# strobecontroller.net
KiCad netlist of a schematic drawn in EAGLE
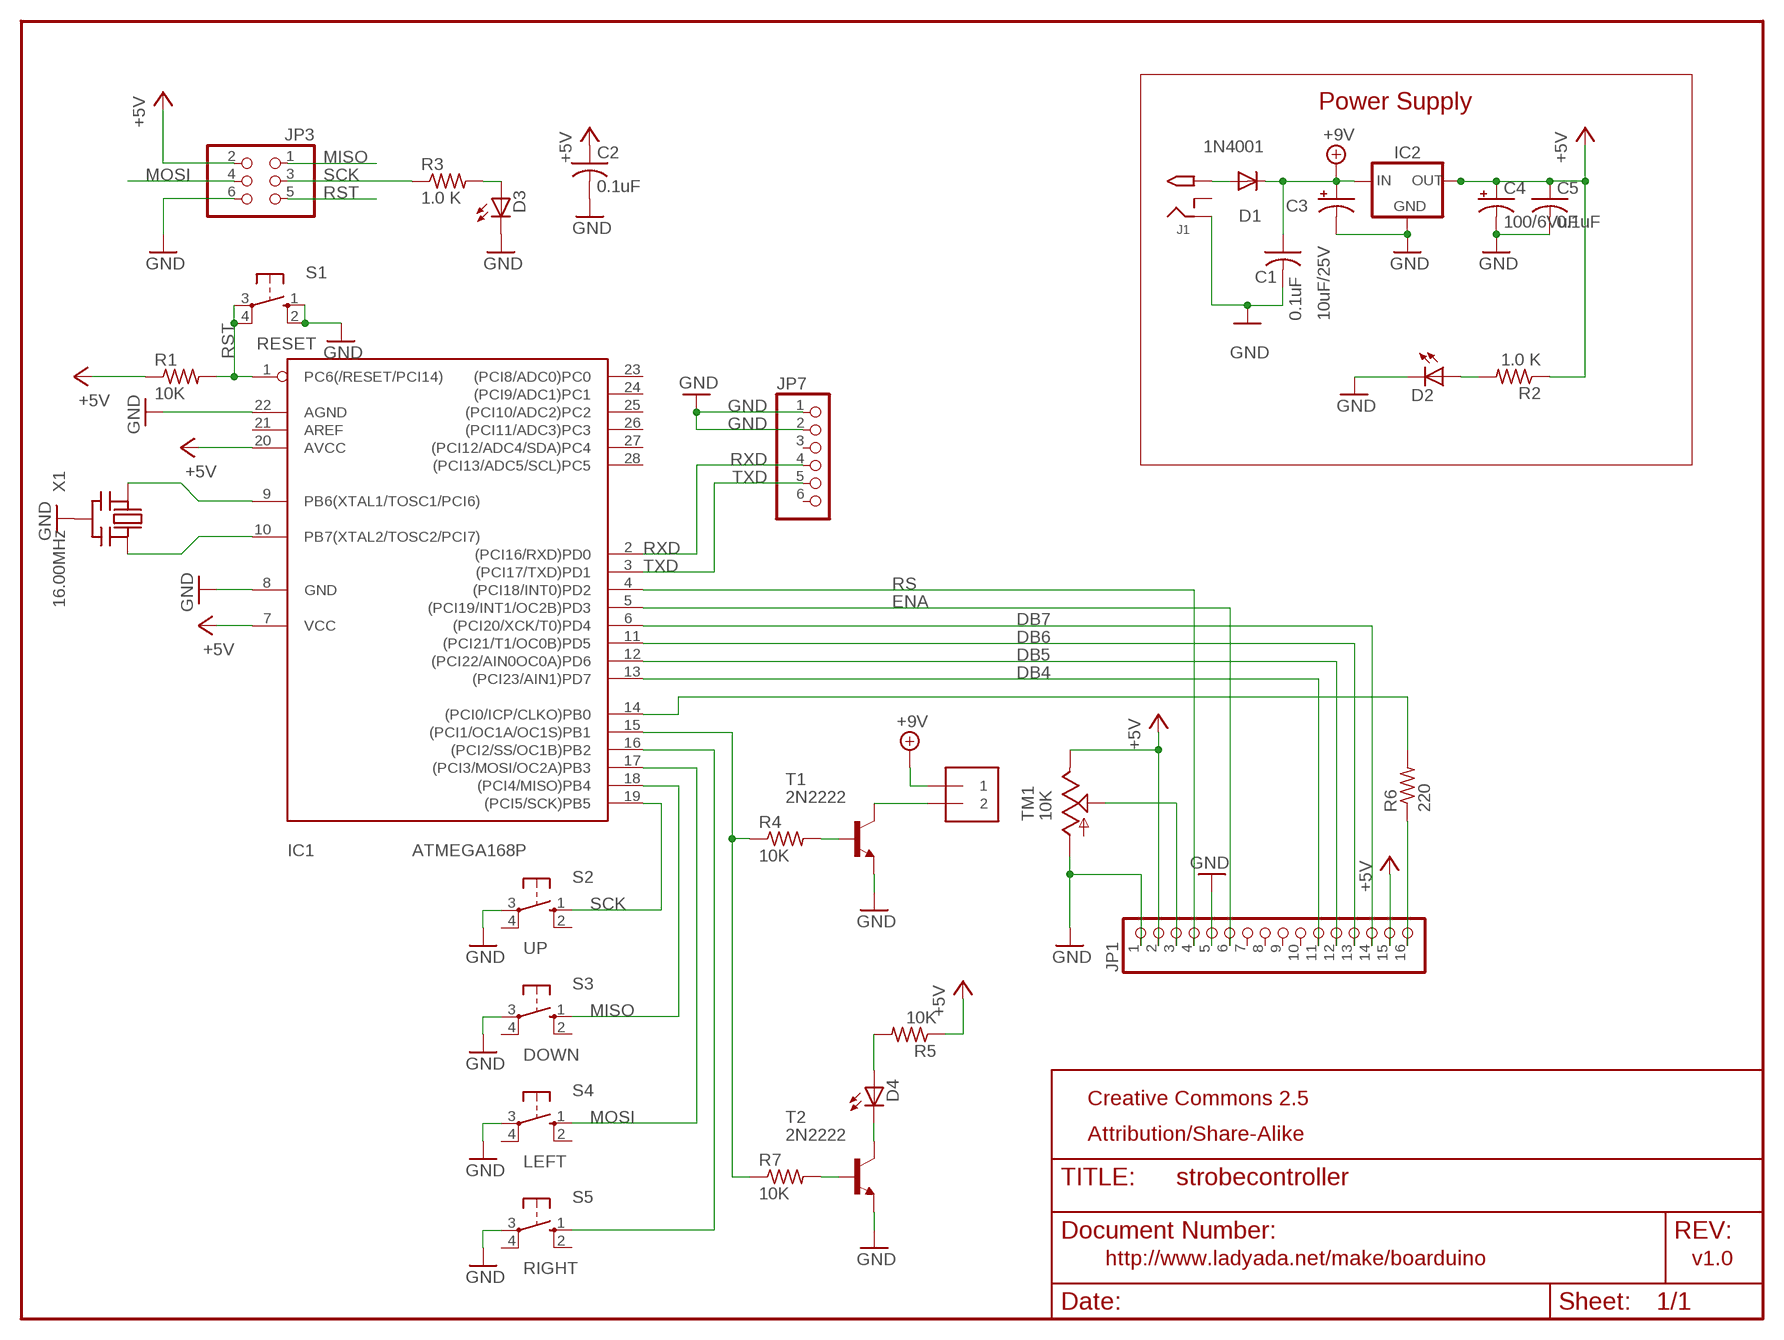
[diagram p0: schematic, sheet 1]

(export (version "E")
  (design (tool "Eeschema 10.0.6"))
  (components
    (comp (ref "C1")
      (value "0.1uF")
      (footprint "eagle-import:C025-025X050")
      (libsource (lib "eagle-import") (part "C-US025-025X050"))
    )
    (comp (ref "C2")
      (value "0.1uF")
      (footprint "eagle-import:C025-025X050")
      (libsource (lib "eagle-import") (part "C-US025-025X050"))
    )
    (comp (ref "C3")
      (value "10uF/25V")
      (footprint "eagle-import:E2,5-6")
      (libsource (lib "eagle-import") (part "CPOL-USE2.5-6"))
    )
    (comp (ref "C4")
      (value "100/6VuF")
      (footprint "eagle-import:E2,5-6")
      (libsource (lib "eagle-import") (part "CPOL-USE2.5-6"))
    )
    (comp (ref "C5")
      (value "0.1uF")
      (footprint "eagle-import:C025-025X050")
      (libsource (lib "eagle-import") (part "C-US025-025X050"))
    )
    (comp (ref "D1")
      (value "1N4001")
      (footprint "eagle-import:DO41-10")
      (libsource (lib "eagle-import") (part "1N4004"))
    )
    (comp (ref "D2")
      (value "Red")
      (footprint "eagle-import:LED3MM")
      (libsource (lib "eagle-import") (part "LED3MM"))
    )
    (comp (ref "D3")
      (value "Green")
      (footprint "eagle-import:LED3MM")
      (libsource (lib "eagle-import") (part "LED3MM"))
    )
    (comp (ref "D4")
      (value "Red")
      (footprint "eagle-import:LED3MM")
      (libsource (lib "eagle-import") (part "LED3MM"))
    )
    (comp (ref "IC1")
      (value "ATMEGA168P")
      (footprint "eagle-import:DIL28_3")
      (libsource (lib "eagle-import") (part "ATMEGA168PROUND"))
    )
    (comp (ref "IC2")
      (value "78XXS")
      (footprint "eagle-import:78XXS")
      (libsource (lib "eagle-import") (part "78XXS"))
    )
    (comp (ref "J1")
      (value "2.1MMJACK")
      (footprint "eagle-import:PJ-102A")
      (libsource (lib "eagle-import") (part "2.1MMJACK"))
    )
    (comp (ref "J2")
      (value "1X2-3.5MM")
      (footprint "eagle-import:1X2-3.5MM")
      (libsource (lib "eagle-import") (part "1X2-3.5MM"))
    )
    (comp (ref "JP1")
      (value "PINHD-1X16")
      (footprint "eagle-import:1X16")
      (libsource (lib "eagle-import") (part "PINHD-1X16"))
    )
    (comp (ref "JP3")
      (value "PINHD-2X3")
      (footprint "eagle-import:2X03")
      (libsource (lib "eagle-import") (part "PINHD-2X3"))
    )
    (comp (ref "JP7")
      (value "PINHD-1X6CLEAN")
      (footprint "eagle-import:1X06-CLEAN")
      (libsource (lib "eagle-import") (part "PINHD-1X6CLEAN"))
    )
    (comp (ref "R1")
      (value "10K")
      (footprint "eagle-import:0207_5V")
      (libsource (lib "eagle-import") (part "rcl-ez_R-US_0207/5V"))
    )
    (comp (ref "R2")
      (value "1.0 K")
      (footprint "eagle-import:0207_5V")
      (libsource (lib "eagle-import") (part "R-US_0207/5V"))
    )
    (comp (ref "R3")
      (value "1.0 K")
      (footprint "eagle-import:0207_5V")
      (libsource (lib "eagle-import") (part "R-US_0207/5V"))
    )
    (comp (ref "R4")
      (value "10K")
      (footprint "eagle-import:0207_5V")
      (libsource (lib "eagle-import") (part "rcl-ez_R-US_0207/5V"))
    )
    (comp (ref "R5")
      (value "10K")
      (footprint "eagle-import:0207_5V")
      (libsource (lib "eagle-import") (part "rcl-ez_R-US_0207/5V"))
    )
    (comp (ref "R6")
      (value "220")
      (footprint "eagle-import:0207_5V")
      (libsource (lib "eagle-import") (part "rcl-ez_R-US_0207/5V"))
    )
    (comp (ref "R7")
      (value "10K")
      (footprint "eagle-import:0207_5V")
      (libsource (lib "eagle-import") (part "rcl-ez_R-US_0207/5V"))
    )
    (comp (ref "S1")
      (value "RESET")
      (footprint "eagle-import:B3F-10XX")
      (libsource (lib "eagle-import") (part "10-XX"))
    )
    (comp (ref "S2")
      (value "UP")
      (footprint "eagle-import:B3F-10XX")
      (libsource (lib "eagle-import") (part "10-XX"))
    )
    (comp (ref "S3")
      (value "DOWN")
      (footprint "eagle-import:B3F-10XX")
      (libsource (lib "eagle-import") (part "10-XX"))
    )
    (comp (ref "S4")
      (value "LEFT")
      (footprint "eagle-import:B3F-10XX")
      (libsource (lib "eagle-import") (part "10-XX"))
    )
    (comp (ref "S5")
      (value "RIGHT")
      (footprint "eagle-import:B3F-10XX")
      (libsource (lib "eagle-import") (part "10-XX"))
    )
    (comp (ref "T1")
      (value "2N2222")
      (footprint "eagle-import:TO92-EBC-OVAL")
      (libsource (lib "eagle-import") (part "2N2222"))
    )
    (comp (ref "T2")
      (value "2N2222")
      (footprint "eagle-import:TO92-EBC-OVAL")
      (libsource (lib "eagle-import") (part "2N2222"))
    )
    (comp (ref "TM1")
      (value "10K")
      (footprint "eagle-import:6MM")
      (libsource (lib "eagle-import") (part "TRIM"))
    )
    (comp (ref "X1")
      (value "16.00MHz")
      (footprint "eagle-import:CERM_OSC")
      (libsource (lib "eagle-import") (part "CERMOSCILL"))
    )
  )
  (nets
    (net (code "1") (name "+5V") (class "Default")
      (node (ref "C2") (pin "1") (pinfunction "1_1") (pintype "passive"))
      (node (ref "C4") (pin "+") (pinfunction "+_+") (pintype "passive"))
      (node (ref "C5") (pin "1") (pinfunction "1_1") (pintype "passive"))
      (node (ref "IC1") (pin "20") (pinfunction "AVCC_20") (pintype "bidirectional"))
      (node (ref "IC1") (pin "7") (pinfunction "VCC_7") (pintype "bidirectional"))
      (node (ref "IC2") (pin "OUT") (pinfunction "OUT_OUT") (pintype "passive"))
      (node (ref "JP1") (pin "15") (pinfunction "15_15") (pintype "passive"))
      (node (ref "JP1") (pin "2") (pinfunction "2_2") (pintype "passive"))
      (node (ref "JP3") (pin "2") (pinfunction "2_2") (pintype "passive"))
      (node (ref "R1") (pin "1") (pinfunction "1_1") (pintype "passive"))
      (node (ref "R2") (pin "1") (pinfunction "1_1") (pintype "passive"))
      (node (ref "R5") (pin "1") (pinfunction "1_1") (pintype "passive"))
      (node (ref "TM1") (pin "E") (pinfunction "E_E") (pintype "passive"))
    )
    (net (code "2") (name "+9V") (class "Default")
      (node (ref "C1") (pin "1") (pinfunction "1_1") (pintype "passive"))
      (node (ref "C3") (pin "+") (pinfunction "+_+") (pintype "passive"))
      (node (ref "D1") (pin "C") (pinfunction "C_C") (pintype "passive"))
      (node (ref "IC2") (pin "IN") (pinfunction "IN_IN") (pintype "input"))
      (node (ref "J2") (pin "1") (pinfunction "1_1") (pintype "passive"))
    )
    (net (code "3") (name "/DB4") (class "Default")
      (node (ref "IC1") (pin "13") (pinfunction "(PCI23/AIN1)PD7_13") (pintype "bidirectional"))
      (node (ref "JP1") (pin "11") (pinfunction "11_11") (pintype "passive"))
    )
    (net (code "4") (name "/DB5") (class "Default")
      (node (ref "IC1") (pin "12") (pinfunction "(PCI22/AIN0OC0A)PD6_12") (pintype "bidirectional"))
      (node (ref "JP1") (pin "12") (pinfunction "12_12") (pintype "passive"))
    )
    (net (code "5") (name "/DB6") (class "Default")
      (node (ref "IC1") (pin "11") (pinfunction "(PCI21/T1/OC0B)PD5_11") (pintype "bidirectional"))
      (node (ref "JP1") (pin "13") (pinfunction "13_13") (pintype "passive"))
    )
    (net (code "6") (name "/DB7") (class "Default")
      (node (ref "IC1") (pin "6") (pinfunction "(PCI20/XCK/T0)PD4_6") (pintype "bidirectional"))
      (node (ref "JP1") (pin "14") (pinfunction "14_14") (pintype "passive"))
    )
    (net (code "7") (name "/ENA") (class "Default")
      (node (ref "IC1") (pin "5") (pinfunction "(PCI19/INT1/OC2B)PD3_5") (pintype "bidirectional"))
      (node (ref "JP1") (pin "6") (pinfunction "6_6") (pintype "passive"))
    )
    (net (code "8") (name "/MISO") (class "Default")
      (node (ref "IC1") (pin "18") (pinfunction "(PCI4/MISO)PB4_18") (pintype "bidirectional"))
      (node (ref "JP3") (pin "1") (pinfunction "1_1") (pintype "passive"))
      (node (ref "S3") (pin "1") (pinfunction "S_1") (pintype "passive"))
    )
    (net (code "9") (name "/MOSI") (class "Default")
      (node (ref "IC1") (pin "17") (pinfunction "(PCI3/MOSI/OC2A)PB3_17") (pintype "bidirectional"))
      (node (ref "JP3") (pin "4") (pinfunction "4_4") (pintype "passive"))
      (node (ref "S4") (pin "1") (pinfunction "S_1") (pintype "passive"))
    )
    (net (code "10") (name "/RS") (class "Default")
      (node (ref "IC1") (pin "4") (pinfunction "(PCI18/INT0)PD2_4") (pintype "bidirectional"))
      (node (ref "JP1") (pin "4") (pinfunction "4_4") (pintype "passive"))
    )
    (net (code "11") (name "/RST") (class "Default")
      (node (ref "IC1") (pin "1") (pinfunction "PC6(/RESET/PCI14)_1") (pintype "bidirectional"))
      (node (ref "JP3") (pin "5") (pinfunction "5_5") (pintype "passive"))
      (node (ref "R1") (pin "2") (pinfunction "2_2") (pintype "passive"))
      (node (ref "S1") (pin "3") (pinfunction "P_3") (pintype "passive"))
      (node (ref "S1") (pin "4") (pinfunction "P1_4") (pintype "passive"))
    )
    (net (code "12") (name "/RXD") (class "Default")
      (node (ref "IC1") (pin "2") (pinfunction "(PCI16/RXD)PD0_2") (pintype "bidirectional"))
      (node (ref "JP7") (pin "4") (pinfunction "4_4") (pintype "passive"))
    )
    (net (code "13") (name "/SCK") (class "Default")
      (node (ref "IC1") (pin "19") (pinfunction "(PCI5/SCK)PB5_19") (pintype "bidirectional"))
      (node (ref "JP3") (pin "3") (pinfunction "3_3") (pintype "passive"))
      (node (ref "R3") (pin "1") (pinfunction "1_1") (pintype "passive"))
      (node (ref "S2") (pin "1") (pinfunction "S_1") (pintype "passive"))
    )
    (net (code "14") (name "/TXD") (class "Default")
      (node (ref "IC1") (pin "3") (pinfunction "(PCI17/TXD)PD1_3") (pintype "bidirectional"))
      (node (ref "JP7") (pin "5") (pinfunction "5_5") (pintype "passive"))
    )
    (net (code "15") (name "GND") (class "Default")
      (node (ref "C1") (pin "2") (pinfunction "2_2") (pintype "passive"))
      (node (ref "C2") (pin "2") (pinfunction "2_2") (pintype "passive"))
      (node (ref "C3") (pin "-") (pinfunction "-_-") (pintype "passive"))
      (node (ref "C4") (pin "-") (pinfunction "-_-") (pintype "passive"))
      (node (ref "C5") (pin "2") (pinfunction "2_2") (pintype "passive"))
      (node (ref "D2") (pin "K") (pinfunction "C_K") (pintype "passive"))
      (node (ref "D3") (pin "K") (pinfunction "C_K") (pintype "passive"))
      (node (ref "IC1") (pin "22") (pinfunction "AGND_22") (pintype "bidirectional"))
      (node (ref "IC1") (pin "8") (pinfunction "GND_8") (pintype "bidirectional"))
      (node (ref "IC2") (pin "GND") (pinfunction "GND_GND") (pintype "input"))
      (node (ref "J1") (pin "RING") (pinfunction "RING_RING") (pintype "bidirectional"))
      (node (ref "JP1") (pin "1") (pinfunction "1_1") (pintype "passive"))
      (node (ref "JP1") (pin "5") (pinfunction "5_5") (pintype "passive"))
      (node (ref "JP3") (pin "6") (pinfunction "6_6") (pintype "passive"))
      (node (ref "JP7") (pin "1") (pinfunction "1_1") (pintype "passive"))
      (node (ref "JP7") (pin "2") (pinfunction "2_2") (pintype "passive"))
      (node (ref "S1") (pin "1") (pinfunction "S_1") (pintype "passive"))
      (node (ref "S1") (pin "2") (pinfunction "S1_2") (pintype "passive"))
      (node (ref "S2") (pin "3") (pinfunction "P_3") (pintype "passive"))
      (node (ref "S3") (pin "3") (pinfunction "P_3") (pintype "passive"))
      (node (ref "S4") (pin "3") (pinfunction "P_3") (pintype "passive"))
      (node (ref "S5") (pin "3") (pinfunction "P_3") (pintype "passive"))
      (node (ref "T1") (pin "E") (pinfunction "E_E") (pintype "passive"))
      (node (ref "T2") (pin "E") (pinfunction "E_E") (pintype "passive"))
      (node (ref "TM1") (pin "A") (pinfunction "A_A") (pintype "passive"))
      (node (ref "X1") (pin "P$2") (pinfunction "GND_P$2") (pintype "bidirectional"))
    )
    (net (code "16") (name "Net-(D1-PadA)") (class "Default")
      (node (ref "D1") (pin "A") (pinfunction "A_A") (pintype "passive"))
      (node (ref "J1") (pin "TIP") (pinfunction "TIP_TIP") (pintype "bidirectional"))
    )
    (net (code "17") (name "Net-(D2-PadA)") (class "Default")
      (node (ref "D2") (pin "A") (pinfunction "A_A") (pintype "passive"))
      (node (ref "R2") (pin "2") (pinfunction "2_2") (pintype "passive"))
    )
    (net (code "18") (name "Net-(D3-PadA)") (class "Default")
      (node (ref "D3") (pin "A") (pinfunction "A_A") (pintype "passive"))
      (node (ref "R3") (pin "2") (pinfunction "2_2") (pintype "passive"))
    )
    (net (code "19") (name "Net-(D4-C)") (class "Default")
      (node (ref "D4") (pin "K") (pinfunction "C_K") (pintype "passive"))
      (node (ref "T2") (pin "C") (pinfunction "C_C") (pintype "passive"))
    )
    (net (code "20") (name "Net-(D4-PadA)") (class "Default")
      (node (ref "D4") (pin "A") (pinfunction "A_A") (pintype "passive"))
      (node (ref "R5") (pin "2") (pinfunction "2_2") (pintype "passive"))
    )
    (net (code "21") (name "Net-(IC1-(PCI0{slash}ICP{slash}CLKO)PB0)") (class "Default")
      (node (ref "IC1") (pin "14") (pinfunction "(PCI0/ICP/CLKO)PB0_14") (pintype "bidirectional"))
      (node (ref "R6") (pin "2") (pinfunction "2_2") (pintype "passive"))
    )
    (net (code "22") (name "Net-(IC1-(PCI1{slash}OC1A{slash}OC1S)PB1)") (class "Default")
      (node (ref "IC1") (pin "15") (pinfunction "(PCI1/OC1A/OC1S)PB1_15") (pintype "bidirectional"))
      (node (ref "R4") (pin "1") (pinfunction "1_1") (pintype "passive"))
      (node (ref "R7") (pin "1") (pinfunction "1_1") (pintype "passive"))
    )
    (net (code "23") (name "Net-(IC1-(PCI2{slash}SS{slash}OC1B)PB2)") (class "Default")
      (node (ref "IC1") (pin "16") (pinfunction "(PCI2/SS/OC1B)PB2_16") (pintype "bidirectional"))
      (node (ref "S5") (pin "1") (pinfunction "S_1") (pintype "passive"))
    )
    (net (code "24") (name "Net-(IC1-PB6(XTAL1{slash}TOSC1{slash}PCI6))") (class "Default")
      (node (ref "IC1") (pin "9") (pinfunction "PB6(XTAL1/TOSC1/PCI6)_9") (pintype "bidirectional"))
      (node (ref "X1") (pin "P$1") (pinfunction "IN_P$1") (pintype "bidirectional"))
    )
    (net (code "25") (name "Net-(IC1-PB7(XTAL2{slash}TOSC2{slash}PCI7))") (class "Default")
      (node (ref "IC1") (pin "10") (pinfunction "PB7(XTAL2/TOSC2/PCI7)_10") (pintype "bidirectional"))
      (node (ref "X1") (pin "P$3") (pinfunction "OUT_P$3") (pintype "bidirectional"))
    )
    (net (code "26") (name "Net-(J2-Pad2)") (class "Default")
      (node (ref "J2") (pin "2") (pinfunction "2_2") (pintype "passive"))
      (node (ref "T1") (pin "C") (pinfunction "C_C") (pintype "passive"))
    )
    (net (code "27") (name "Net-(JP1-Pad3)") (class "Default")
      (node (ref "JP1") (pin "3") (pinfunction "3_3") (pintype "passive"))
      (node (ref "TM1") (pin "S") (pinfunction "S_S") (pintype "passive"))
    )
    (net (code "28") (name "Net-(JP1-Pad16)") (class "Default")
      (node (ref "JP1") (pin "16") (pinfunction "16_16") (pintype "passive"))
      (node (ref "R6") (pin "1") (pinfunction "1_1") (pintype "passive"))
    )
    (net (code "29") (name "Net-(R4-Pad2)") (class "Default")
      (node (ref "R4") (pin "2") (pinfunction "2_2") (pintype "passive"))
      (node (ref "T1") (pin "B") (pinfunction "B_B") (pintype "passive"))
    )
    (net (code "30") (name "Net-(R7-Pad2)") (class "Default")
      (node (ref "R7") (pin "2") (pinfunction "2_2") (pintype "passive"))
      (node (ref "T2") (pin "B") (pinfunction "B_B") (pintype "passive"))
    )
    (net (code "31") (name "unconnected-(IC1-(PCI8{slash}ADC0)PC0-Pad23)") (class "Default")
      (node (ref "IC1") (pin "23") (pinfunction "(PCI8/ADC0)PC0_23") (pintype "bidirectional"))
    )
    (net (code "32") (name "unconnected-(IC1-(PCI9{slash}ADC1)PC1-Pad24)") (class "Default")
      (node (ref "IC1") (pin "24") (pinfunction "(PCI9/ADC1)PC1_24") (pintype "bidirectional"))
    )
    (net (code "33") (name "unconnected-(IC1-(PCI10{slash}ADC2)PC2-Pad25)") (class "Default")
      (node (ref "IC1") (pin "25") (pinfunction "(PCI10/ADC2)PC2_25") (pintype "bidirectional"))
    )
    (net (code "34") (name "unconnected-(IC1-(PCI11{slash}ADC3)PC3-Pad26)") (class "Default")
      (node (ref "IC1") (pin "26") (pinfunction "(PCI11/ADC3)PC3_26") (pintype "bidirectional"))
    )
    (net (code "35") (name "unconnected-(IC1-(PCI12{slash}ADC4{slash}SDA)PC4-Pad27)") (class "Default")
      (node (ref "IC1") (pin "27") (pinfunction "(PCI12/ADC4/SDA)PC4_27") (pintype "bidirectional"))
    )
    (net (code "36") (name "unconnected-(IC1-(PCI13{slash}ADC5{slash}SCL)PC5-Pad28)") (class "Default")
      (node (ref "IC1") (pin "28") (pinfunction "(PCI13/ADC5/SCL)PC5_28") (pintype "bidirectional"))
    )
    (net (code "37") (name "unconnected-(IC1-AREF-Pad21)") (class "Default")
      (node (ref "IC1") (pin "21") (pinfunction "AREF_21") (pintype "bidirectional"))
    )
    (net (code "38") (name "unconnected-(J1-PadRING_SW)") (class "Default")
      (node (ref "J1") (pin "RING_SW") (pinfunction "RING_SW_RING_SW") (pintype "bidirectional"))
    )
    (net (code "39") (name "unconnected-(JP1-Pad7)") (class "Default")
      (node (ref "JP1") (pin "7") (pinfunction "7_7") (pintype "passive"))
    )
    (net (code "40") (name "unconnected-(JP1-Pad8)") (class "Default")
      (node (ref "JP1") (pin "8") (pinfunction "8_8") (pintype "passive"))
    )
    (net (code "41") (name "unconnected-(JP1-Pad9)") (class "Default")
      (node (ref "JP1") (pin "9") (pinfunction "9_9") (pintype "passive"))
    )
    (net (code "42") (name "unconnected-(JP1-Pad10)") (class "Default")
      (node (ref "JP1") (pin "10") (pinfunction "10_10") (pintype "passive"))
    )
    (net (code "43") (name "unconnected-(JP7-Pad3)") (class "Default")
      (node (ref "JP7") (pin "3") (pinfunction "3_3") (pintype "passive"))
    )
    (net (code "44") (name "unconnected-(JP7-Pad6)") (class "Default")
      (node (ref "JP7") (pin "6") (pinfunction "6_6") (pintype "passive"))
    )
    (net (code "45") (name "unconnected-(S2-P1-Pad4)") (class "Default")
      (node (ref "S2") (pin "4") (pinfunction "P1_4") (pintype "passive"))
    )
    (net (code "46") (name "unconnected-(S2-S1-Pad2)") (class "Default")
      (node (ref "S2") (pin "2") (pinfunction "S1_2") (pintype "passive"))
    )
    (net (code "47") (name "unconnected-(S3-P1-Pad4)") (class "Default")
      (node (ref "S3") (pin "4") (pinfunction "P1_4") (pintype "passive"))
    )
    (net (code "48") (name "unconnected-(S3-S1-Pad2)") (class "Default")
      (node (ref "S3") (pin "2") (pinfunction "S1_2") (pintype "passive"))
    )
    (net (code "49") (name "unconnected-(S4-P1-Pad4)") (class "Default")
      (node (ref "S4") (pin "4") (pinfunction "P1_4") (pintype "passive"))
    )
    (net (code "50") (name "unconnected-(S4-S1-Pad2)") (class "Default")
      (node (ref "S4") (pin "2") (pinfunction "S1_2") (pintype "passive"))
    )
    (net (code "51") (name "unconnected-(S5-P1-Pad4)") (class "Default")
      (node (ref "S5") (pin "4") (pinfunction "P1_4") (pintype "passive"))
    )
    (net (code "52") (name "unconnected-(S5-S1-Pad2)") (class "Default")
      (node (ref "S5") (pin "2") (pinfunction "S1_2") (pintype "passive"))
    )
  )
)
